# Ctrl_Enc.net
KiCad netlist of a schematic drawn in EAGLE
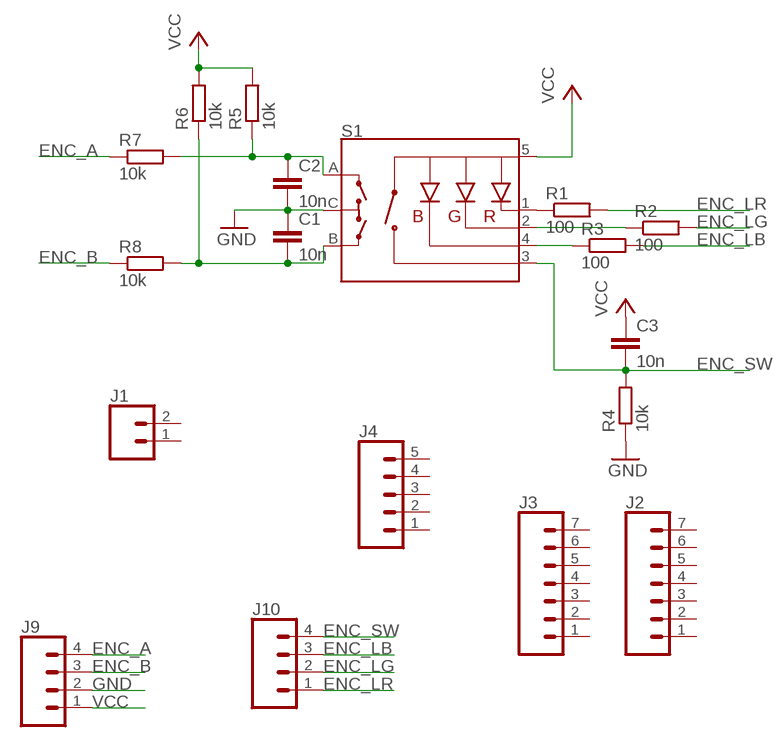
[diagram p0: schematic, sheet 1]

(export (version "E")
  (design (tool "Eeschema 10.0.6"))
  (components
    (comp (ref "C1")
      (value "10n")
      (footprint "eagle-import:C0603")
      (libsource (lib "eagle-import") (part "C-EUC0603"))
    )
    (comp (ref "C2")
      (value "10n")
      (footprint "eagle-import:C0603")
      (libsource (lib "eagle-import") (part "C-EUC0603"))
    )
    (comp (ref "C3")
      (value "10n")
      (footprint "eagle-import:C0603")
      (libsource (lib "eagle-import") (part "C-EUC0603"))
    )
    (comp (ref "J1")
      (value "CONN_02")
      (footprint "eagle-import:1X02")
      (libsource (lib "eagle-import") (part "CONN_02"))
    )
    (comp (ref "J2")
      (value "CONN_07")
      (footprint "eagle-import:1X07")
      (libsource (lib "eagle-import") (part "CONN_07"))
    )
    (comp (ref "J3")
      (value "CONN_07")
      (footprint "eagle-import:1X07")
      (libsource (lib "eagle-import") (part "CONN_07"))
    )
    (comp (ref "J4")
      (value "CONN_05")
      (footprint "eagle-import:1X05")
      (libsource (lib "eagle-import") (part "CONN_05"))
    )
    (comp (ref "J9")
      (value "CONN_04")
      (footprint "eagle-import:1X04")
      (libsource (lib "eagle-import") (part "CONN_04"))
    )
    (comp (ref "J10")
      (value "CONN_04")
      (footprint "eagle-import:1X04")
      (libsource (lib "eagle-import") (part "CONN_04"))
    )
    (comp (ref "R1")
      (value "100")
      (footprint "eagle-import:R0603")
      (libsource (lib "eagle-import") (part "R-EU_R0603"))
    )
    (comp (ref "R2")
      (value "100")
      (footprint "eagle-import:R0603")
      (libsource (lib "eagle-import") (part "R-EU_R0603"))
    )
    (comp (ref "R3")
      (value "100")
      (footprint "eagle-import:R0603")
      (libsource (lib "eagle-import") (part "R-EU_R0603"))
    )
    (comp (ref "R4")
      (value "10k")
      (footprint "eagle-import:R0603")
      (libsource (lib "eagle-import") (part "R-EU_R0603"))
    )
    (comp (ref "R5")
      (value "10k")
      (footprint "eagle-import:R0603")
      (libsource (lib "eagle-import") (part "R-EU_R0603"))
    )
    (comp (ref "R6")
      (value "10k")
      (footprint "eagle-import:R0603")
      (libsource (lib "eagle-import") (part "R-EU_R0603"))
    )
    (comp (ref "R7")
      (value "10k")
      (footprint "eagle-import:R0603")
      (libsource (lib "eagle-import") (part "R-EU_R0603"))
    )
    (comp (ref "R8")
      (value "10k")
      (footprint "eagle-import:R0603")
      (libsource (lib "eagle-import") (part "R-EU_R0603"))
    )
    (comp (ref "S1")
      (value "ENCODER-RGB-SWITCH")
      (footprint "eagle-import:ENCODER_LED_3")
      (libsource (lib "eagle-import") (part "ENCODER-RGB-SWITCH"))
    )
  )
  (nets
    (net (code "1") (name "/ENC_A") (class "Default")
      (node (ref "J9") (pin "4") (pinfunction "4_4") (pintype "passive"))
      (node (ref "R7") (pin "1") (pinfunction "1_1") (pintype "passive"))
    )
    (net (code "2") (name "/ENC_B") (class "Default")
      (node (ref "J9") (pin "3") (pinfunction "3_3") (pintype "passive"))
      (node (ref "R8") (pin "1") (pinfunction "1_1") (pintype "passive"))
    )
    (net (code "3") (name "/ENC_LB") (class "Default")
      (node (ref "J10") (pin "3") (pinfunction "3_3") (pintype "passive"))
      (node (ref "R3") (pin "2") (pinfunction "2_2") (pintype "passive"))
    )
    (net (code "4") (name "/ENC_LG") (class "Default")
      (node (ref "J10") (pin "2") (pinfunction "2_2") (pintype "passive"))
      (node (ref "R2") (pin "2") (pinfunction "2_2") (pintype "passive"))
    )
    (net (code "5") (name "/ENC_LR") (class "Default")
      (node (ref "J10") (pin "1") (pinfunction "1_1") (pintype "passive"))
      (node (ref "R1") (pin "2") (pinfunction "2_2") (pintype "passive"))
    )
    (net (code "6") (name "/ENC_SW") (class "Default")
      (node (ref "C3") (pin "2") (pinfunction "2_2") (pintype "passive"))
      (node (ref "J10") (pin "4") (pinfunction "4_4") (pintype "passive"))
      (node (ref "R4") (pin "2") (pinfunction "2_2") (pintype "passive"))
      (node (ref "S1") (pin "3") (pinfunction "SW_3") (pintype "passive"))
    )
    (net (code "7") (name "GND") (class "Default")
      (node (ref "C1") (pin "1") (pinfunction "1_1") (pintype "passive"))
      (node (ref "C2") (pin "2") (pinfunction "2_2") (pintype "passive"))
      (node (ref "J9") (pin "2") (pinfunction "2_2") (pintype "passive"))
      (node (ref "R4") (pin "1") (pinfunction "1_1") (pintype "passive"))
      (node (ref "S1") (pin "C") (pinfunction "C_C") (pintype "bidirectional"))
    )
    (net (code "8") (name "Net-(C1-Pad2)") (class "Default")
      (node (ref "C1") (pin "2") (pinfunction "2_2") (pintype "passive"))
      (node (ref "R6") (pin "1") (pinfunction "1_1") (pintype "passive"))
      (node (ref "R8") (pin "2") (pinfunction "2_2") (pintype "passive"))
      (node (ref "S1") (pin "B") (pinfunction "B_B") (pintype "bidirectional"))
    )
    (net (code "9") (name "Net-(C2-Pad1)") (class "Default")
      (node (ref "C2") (pin "1") (pinfunction "1_1") (pintype "passive"))
      (node (ref "R5") (pin "1") (pinfunction "1_1") (pintype "passive"))
      (node (ref "R7") (pin "2") (pinfunction "2_2") (pintype "passive"))
      (node (ref "S1") (pin "A") (pinfunction "A_A") (pintype "bidirectional"))
    )
    (net (code "10") (name "Net-(S1--B)") (class "Default")
      (node (ref "R3") (pin "1") (pinfunction "1_1") (pintype "passive"))
      (node (ref "S1") (pin "4") (pinfunction "-B_4") (pintype "passive"))
    )
    (net (code "11") (name "Net-(S1--G)") (class "Default")
      (node (ref "R2") (pin "1") (pinfunction "1_1") (pintype "passive"))
      (node (ref "S1") (pin "2") (pinfunction "-G_2") (pintype "passive"))
    )
    (net (code "12") (name "Net-(S1--R)") (class "Default")
      (node (ref "R1") (pin "1") (pinfunction "1_1") (pintype "passive"))
      (node (ref "S1") (pin "1") (pinfunction "-R_1") (pintype "passive"))
    )
    (net (code "13") (name "VCC") (class "Default")
      (node (ref "C3") (pin "1") (pinfunction "1_1") (pintype "passive"))
      (node (ref "J9") (pin "1") (pinfunction "1_1") (pintype "passive"))
      (node (ref "R5") (pin "2") (pinfunction "2_2") (pintype "passive"))
      (node (ref "R6") (pin "2") (pinfunction "2_2") (pintype "passive"))
      (node (ref "S1") (pin "5") (pinfunction "+_5") (pintype "passive"))
    )
    (net (code "14") (name "unconnected-(J1-Pad1)") (class "Default")
      (node (ref "J1") (pin "1") (pinfunction "1_1") (pintype "passive"))
    )
    (net (code "15") (name "unconnected-(J1-Pad2)") (class "Default")
      (node (ref "J1") (pin "2") (pinfunction "2_2") (pintype "passive"))
    )
    (net (code "16") (name "unconnected-(J2-Pad1)") (class "Default")
      (node (ref "J2") (pin "1") (pinfunction "1_1") (pintype "passive"))
    )
    (net (code "17") (name "unconnected-(J2-Pad2)") (class "Default")
      (node (ref "J2") (pin "2") (pinfunction "2_2") (pintype "passive"))
    )
    (net (code "18") (name "unconnected-(J2-Pad3)") (class "Default")
      (node (ref "J2") (pin "3") (pinfunction "3_3") (pintype "passive"))
    )
    (net (code "19") (name "unconnected-(J2-Pad4)") (class "Default")
      (node (ref "J2") (pin "4") (pinfunction "4_4") (pintype "passive"))
    )
    (net (code "20") (name "unconnected-(J2-Pad5)") (class "Default")
      (node (ref "J2") (pin "5") (pinfunction "5_5") (pintype "passive"))
    )
    (net (code "21") (name "unconnected-(J2-Pad6)") (class "Default")
      (node (ref "J2") (pin "6") (pinfunction "6_6") (pintype "passive"))
    )
    (net (code "22") (name "unconnected-(J2-Pad7)") (class "Default")
      (node (ref "J2") (pin "7") (pinfunction "7_7") (pintype "passive"))
    )
    (net (code "23") (name "unconnected-(J3-Pad1)") (class "Default")
      (node (ref "J3") (pin "1") (pinfunction "1_1") (pintype "passive"))
    )
    (net (code "24") (name "unconnected-(J3-Pad2)") (class "Default")
      (node (ref "J3") (pin "2") (pinfunction "2_2") (pintype "passive"))
    )
    (net (code "25") (name "unconnected-(J3-Pad3)") (class "Default")
      (node (ref "J3") (pin "3") (pinfunction "3_3") (pintype "passive"))
    )
    (net (code "26") (name "unconnected-(J3-Pad4)") (class "Default")
      (node (ref "J3") (pin "4") (pinfunction "4_4") (pintype "passive"))
    )
    (net (code "27") (name "unconnected-(J3-Pad5)") (class "Default")
      (node (ref "J3") (pin "5") (pinfunction "5_5") (pintype "passive"))
    )
    (net (code "28") (name "unconnected-(J3-Pad6)") (class "Default")
      (node (ref "J3") (pin "6") (pinfunction "6_6") (pintype "passive"))
    )
    (net (code "29") (name "unconnected-(J3-Pad7)") (class "Default")
      (node (ref "J3") (pin "7") (pinfunction "7_7") (pintype "passive"))
    )
    (net (code "30") (name "unconnected-(J4-Pad1)") (class "Default")
      (node (ref "J4") (pin "1") (pinfunction "1_1") (pintype "passive"))
    )
    (net (code "31") (name "unconnected-(J4-Pad2)") (class "Default")
      (node (ref "J4") (pin "2") (pinfunction "2_2") (pintype "passive"))
    )
    (net (code "32") (name "unconnected-(J4-Pad3)") (class "Default")
      (node (ref "J4") (pin "3") (pinfunction "3_3") (pintype "passive"))
    )
    (net (code "33") (name "unconnected-(J4-Pad4)") (class "Default")
      (node (ref "J4") (pin "4") (pinfunction "4_4") (pintype "passive"))
    )
    (net (code "34") (name "unconnected-(J4-Pad5)") (class "Default")
      (node (ref "J4") (pin "5") (pinfunction "5_5") (pintype "passive"))
    )
  )
)
